# Power.net
KiCad netlist of a schematic drawn in Altium Designer
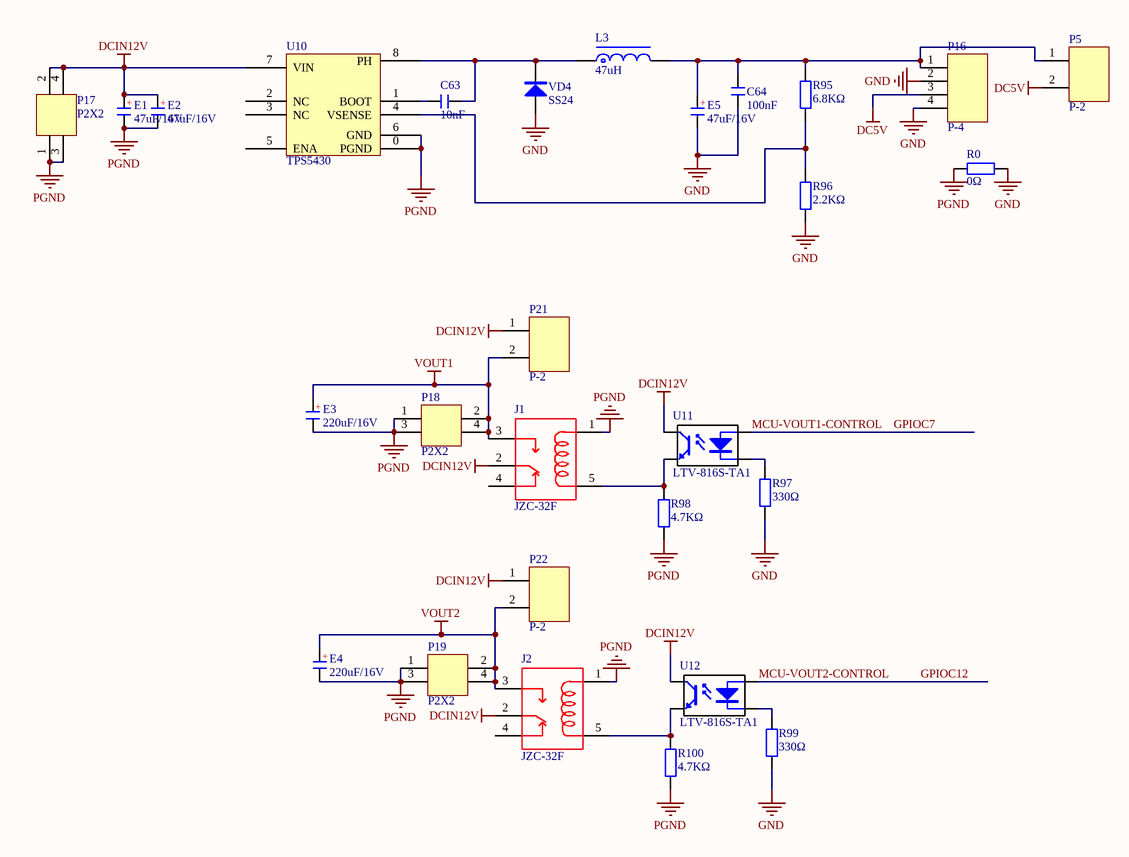
[diagram p0: Power.SchDoc]

(export (version "E")
  (design (tool "Eeschema 10.0.6"))
  (components
    (comp (ref "C63")
      (value "10nF")
      (footprint "C 0603")
      (description "无极性贴片电容")
      (fields (field (name "版权归属") "源创客"))
      (libsource (lib "ZZF_Library") (part "C 10nF"))
    )
    (comp (ref "C64")
      (value "100nF")
      (footprint "C 0603")
      (description "无极性贴片电容")
      (fields (field (name "版权归属") "源创客"))
      (libsource (lib "ZZF_Library") (part "C 100nF"))
    )
    (comp (ref "E1")
      (value "47uF/16V")
      (footprint "CD C(6032)")
      (description "贴片钽电容")
      (fields (field (name "版权归属") "源创客"))
      (libsource (lib "ZZF_Library") (part "C-CD 47uF/16V"))
    )
    (comp (ref "E2")
      (value "47uF/16V")
      (footprint "CD C(6032)")
      (description "贴片钽电容")
      (fields (field (name "版权归属") "源创客"))
      (libsource (lib "ZZF_Library") (part "C-CD 47uF/16V"))
    )
    (comp (ref "E3")
      (value "220uF/16V")
      (footprint "CD E(7343H)")
      (description "贴片钽电容")
      (fields (field (name "版权归属") "源创客"))
      (libsource (lib "ZZF_Library") (part "C-CD 220uF/16V"))
    )
    (comp (ref "E4")
      (value "220uF/16V")
      (footprint "CD E(7343H)")
      (description "贴片钽电容")
      (fields (field (name "版权归属") "源创客"))
      (libsource (lib "ZZF_Library") (part "C-CD 220uF/16V"))
    )
    (comp (ref "E5")
      (value "47uF/16V")
      (footprint "CD C(6032)")
      (description "贴片钽电容")
      (fields (field (name "版权归属") "源创客"))
      (libsource (lib "ZZF_Library") (part "C-CD 47uF/16V"))
    )
    (comp (ref "J1")
      (value "JZC-32F")
      (footprint "RELAY-ThroughHole")
      (description "继电器12V10A")
      (libsource (lib "ZZF_Library") (part "RELAY JZC-32F"))
    )
    (comp (ref "J2")
      (value "JZC-32F")
      (footprint "RELAY-ThroughHole")
      (description "继电器12V10A")
      (libsource (lib "ZZF_Library") (part "RELAY JZC-32F"))
    )
    (comp (ref "L3")
      (value "47uH")
      (footprint "L CD75")
      (description "贴片功率电感")
      (fields (field (name "版权归属") "源创客"))
      (libsource (lib "ZZF_Library") (part "L-CD  47uH"))
    )
    (comp (ref "P5")
      (value "P-2")
      (footprint "P HDR2.54-1X2")
      (description "2脚接插件")
      (libsource (lib "ZZF_Library") (part "P-2"))
    )
    (comp (ref "P16")
      (value "P-4")
      (footprint "P XH2.54-4")
      (description "4脚接插件")
      (libsource (lib "ZZF_Library") (part "P-4"))
    )
    (comp (ref "P17")
      (value "P2X2")
      (footprint "P 5557ATX4.2-2X2H")
      (description "2X2脚接插件")
      (libsource (lib "") (part "P-2X2_1"))
    )
    (comp (ref "P18")
      (value "P2X2")
      (footprint "P 5557ATX4.2-2X2H")
      (description "2X2脚接插件")
      (libsource (lib "ZZF_Library") (part "P-2X2"))
    )
    (comp (ref "P19")
      (value "P2X2")
      (footprint "P 5557ATX4.2-2X2H")
      (description "2X2脚接插件")
      (libsource (lib "ZZF_Library") (part "P-2X2"))
    )
    (comp (ref "P21")
      (value "P-2")
      (footprint "P HDR2.54-1X2")
      (description "2脚接插件")
      (libsource (lib "ZZF_Library") (part "P-2"))
    )
    (comp (ref "P22")
      (value "P-2")
      (footprint "P HDR2.54-1X2")
      (description "2脚接插件")
      (libsource (lib "ZZF_Library") (part "P-2"))
    )
    (comp (ref "R0")
      (value "0Ω")
      (footprint "R 0805")
      (description "贴片电阻")
      (fields (field (name "版权归属") "源创客"))
      (libsource (lib "ZZF_Library") (part "R 0Ω"))
    )
    (comp (ref "R95")
      (value "6.8KΩ")
      (footprint "R 0603")
      (description "贴片电阻")
      (fields (field (name "版权归属") "源创客"))
      (libsource (lib "ZZF_Library") (part "R 6.8KΩ"))
    )
    (comp (ref "R96")
      (value "2.2KΩ")
      (footprint "R 0603")
      (description "贴片电阻")
      (fields (field (name "版权归属") "源创客"))
      (libsource (lib "ZZF_Library") (part "R 2.2KΩ"))
    )
    (comp (ref "R97")
      (value "330Ω")
      (footprint "R 0805")
      (description "贴片电阻")
      (fields (field (name "版权归属") "源创客"))
      (libsource (lib "ZZF_Library") (part "R 330Ω"))
    )
    (comp (ref "R98")
      (value "4.7KΩ")
      (footprint "R 0603")
      (description "贴片电阻")
      (fields (field (name "版权归属") "源创客"))
      (libsource (lib "ZZF_Library") (part "R 4.7KΩ"))
    )
    (comp (ref "R99")
      (value "330Ω")
      (footprint "R 0805")
      (description "贴片电阻")
      (fields (field (name "版权归属") "源创客"))
      (libsource (lib "ZZF_Library") (part "R 330Ω"))
    )
    (comp (ref "R100")
      (value "4.7KΩ")
      (footprint "R 0603")
      (description "贴片电阻")
      (fields (field (name "版权归属") "源创客"))
      (libsource (lib "ZZF_Library") (part "R 4.7KΩ"))
    )
    (comp (ref "U10")
      (value "TPS5430")
      (footprint "SOP8-EP")
      (description "DCDC芯片3A")
      (libsource (lib "ZZF_Library") (part "TPS5430"))
    )
    (comp (ref "U11")
      (value "LTV-816S-TA1")
      (footprint "Optocoupler-SMD4")
      (description "光耦芯片")
      (libsource (lib "ZZF_Library") (part "Optocoupler LTV-816S-TA1"))
    )
    (comp (ref "U12")
      (value "LTV-816S-TA1")
      (footprint "Optocoupler-SMD4")
      (description "光耦芯片")
      (libsource (lib "ZZF_Library") (part "Optocoupler LTV-816S-TA1"))
    )
    (comp (ref "VD4")
      (value "SS24")
      (footprint "D SMB")
      (description "肖特基二极管")
      (fields (field (name "版权归属") "源创客"))
      (libsource (lib "ZZF_Library") (part "SS24"))
    )
  )
  (nets
    (net (code "1") (name "/GPIOC7") (class "Default")
      (node (ref "U11") (pin "1") (pinfunction "1_1") (pintype "passive"))
    )
    (net (code "2") (name "/GPIOC12") (class "Default")
      (node (ref "U12") (pin "1") (pinfunction "1_1") (pintype "passive"))
    )
    (net (code "3") (name "DC5V") (class "Default")
      (node (ref "P16") (pin "3") (pinfunction "3_3") (pintype "passive"))
      (node (ref "P5") (pin "2") (pinfunction "2_2") (pintype "passive"))
    )
    (net (code "4") (name "DCIN12V") (class "Default")
      (node (ref "E1") (pin "A") (pinfunction "+_A") (pintype "passive"))
      (node (ref "E2") (pin "A") (pinfunction "+_A") (pintype "passive"))
      (node (ref "J1") (pin "2") (pinfunction "IN-_2") (pintype "passive"))
      (node (ref "J2") (pin "2") (pinfunction "IN-_2") (pintype "passive"))
      (node (ref "P17") (pin "2") (pinfunction "2_2") (pintype "passive"))
      (node (ref "P17") (pin "4") (pinfunction "4_4") (pintype "passive"))
      (node (ref "P21") (pin "1") (pinfunction "1_1") (pintype "passive"))
      (node (ref "P22") (pin "1") (pinfunction "1_1") (pintype "passive"))
      (node (ref "U10") (pin "7") (pinfunction "VIN_7") (pintype "passive"))
      (node (ref "U11") (pin "4") (pinfunction "4_4") (pintype "passive"))
      (node (ref "U12") (pin "4") (pinfunction "4_4") (pintype "passive"))
    )
    (net (code "5") (name "GND") (class "Default")
      (node (ref "C64") (pin "1") (pinfunction "1_1") (pintype "passive"))
      (node (ref "E5") (pin "K") (pinfunction "-_K") (pintype "passive"))
      (node (ref "P16") (pin "2") (pinfunction "2_2") (pintype "passive"))
      (node (ref "P16") (pin "4") (pinfunction "4_4") (pintype "passive"))
      (node (ref "R0") (pin "2") (pinfunction "2_2") (pintype "passive"))
      (node (ref "R96") (pin "1") (pinfunction "1_1") (pintype "passive"))
      (node (ref "R97") (pin "1") (pinfunction "1_1") (pintype "passive"))
      (node (ref "R99") (pin "1") (pinfunction "1_1") (pintype "passive"))
      (node (ref "VD4") (pin "A") (pinfunction "A_A") (pintype "passive"))
    )
    (net (code "6") (name "Net-(E5-+)") (class "Default")
      (node (ref "C64") (pin "2") (pinfunction "2_2") (pintype "passive"))
      (node (ref "E5") (pin "A") (pinfunction "+_A") (pintype "passive"))
      (node (ref "L3") (pin "2") (pinfunction "2_2") (pintype "passive"))
      (node (ref "P16") (pin "1") (pinfunction "1_1") (pintype "passive"))
      (node (ref "P5") (pin "1") (pinfunction "1_1") (pintype "passive"))
      (node (ref "R95") (pin "2") (pinfunction "2_2") (pintype "passive"))
    )
    (net (code "7") (name "Net-(J1-OUT-)") (class "Default")
      (node (ref "J1") (pin "5") (pinfunction "OUT-_5") (pintype "passive"))
      (node (ref "R98") (pin "2") (pinfunction "2_2") (pintype "passive"))
      (node (ref "U11") (pin "3") (pinfunction "3_3") (pintype "passive"))
    )
    (net (code "8") (name "Net-(J2-OUT-)") (class "Default")
      (node (ref "J2") (pin "5") (pinfunction "OUT-_5") (pintype "passive"))
      (node (ref "R100") (pin "2") (pinfunction "2_2") (pintype "passive"))
      (node (ref "U12") (pin "3") (pinfunction "3_3") (pintype "passive"))
    )
    (net (code "9") (name "Net-(R97-Pad2)") (class "Default")
      (node (ref "R97") (pin "2") (pinfunction "2_2") (pintype "passive"))
      (node (ref "U11") (pin "2") (pinfunction "2_2") (pintype "passive"))
    )
    (net (code "10") (name "Net-(R99-Pad2)") (class "Default")
      (node (ref "R99") (pin "2") (pinfunction "2_2") (pintype "passive"))
      (node (ref "U12") (pin "2") (pinfunction "2_2") (pintype "passive"))
    )
    (net (code "11") (name "Net-(U10-BOOT)") (class "Default")
      (node (ref "C63") (pin "1") (pinfunction "1_1") (pintype "passive"))
      (node (ref "U10") (pin "1") (pinfunction "BOOT_1") (pintype "passive"))
    )
    (net (code "12") (name "Net-(U10-PH)") (class "Default")
      (node (ref "C63") (pin "2") (pinfunction "2_2") (pintype "passive"))
      (node (ref "L3") (pin "1") (pinfunction "1_1") (pintype "passive"))
      (node (ref "U10") (pin "8") (pinfunction "PH_8") (pintype "passive"))
      (node (ref "VD4") (pin "K") (pinfunction "K_K") (pintype "passive"))
    )
    (net (code "13") (name "Net-(U10-VSENSE)") (class "Default")
      (node (ref "R95") (pin "1") (pinfunction "1_1") (pintype "passive"))
      (node (ref "R96") (pin "2") (pinfunction "2_2") (pintype "passive"))
      (node (ref "U10") (pin "4") (pinfunction "VSENSE_4") (pintype "passive"))
    )
    (net (code "14") (name "PGND") (class "Default")
      (node (ref "E1") (pin "K") (pinfunction "-_K") (pintype "passive"))
      (node (ref "E2") (pin "K") (pinfunction "-_K") (pintype "passive"))
      (node (ref "E3") (pin "K") (pinfunction "-_K") (pintype "passive"))
      (node (ref "E4") (pin "K") (pinfunction "-_K") (pintype "passive"))
      (node (ref "J1") (pin "1") (pinfunction "OUT+_1") (pintype "passive"))
      (node (ref "J2") (pin "1") (pinfunction "OUT+_1") (pintype "passive"))
      (node (ref "P17") (pin "1") (pinfunction "1_1") (pintype "passive"))
      (node (ref "P17") (pin "3") (pinfunction "3_3") (pintype "passive"))
      (node (ref "P18") (pin "1") (pinfunction "1_1") (pintype "passive"))
      (node (ref "P18") (pin "3") (pinfunction "3_3") (pintype "passive"))
      (node (ref "P19") (pin "1") (pinfunction "1_1") (pintype "passive"))
      (node (ref "P19") (pin "3") (pinfunction "3_3") (pintype "passive"))
      (node (ref "R0") (pin "1") (pinfunction "1_1") (pintype "passive"))
      (node (ref "R100") (pin "1") (pinfunction "1_1") (pintype "passive"))
      (node (ref "R98") (pin "1") (pinfunction "1_1") (pintype "passive"))
      (node (ref "U10") (pin "0") (pinfunction "PGND_0") (pintype "passive"))
      (node (ref "U10") (pin "6") (pinfunction "GND_6") (pintype "passive"))
    )
    (net (code "15") (name "VOUT1") (class "Default")
      (node (ref "E3") (pin "A") (pinfunction "+_A") (pintype "passive"))
      (node (ref "J1") (pin "3") (pinfunction "IN+_3") (pintype "passive"))
      (node (ref "P18") (pin "2") (pinfunction "2_2") (pintype "passive"))
      (node (ref "P18") (pin "4") (pinfunction "4_4") (pintype "passive"))
      (node (ref "P21") (pin "2") (pinfunction "2_2") (pintype "passive"))
    )
    (net (code "16") (name "VOUT2") (class "Default")
      (node (ref "E4") (pin "A") (pinfunction "+_A") (pintype "passive"))
      (node (ref "J2") (pin "3") (pinfunction "IN+_3") (pintype "passive"))
      (node (ref "P19") (pin "2") (pinfunction "2_2") (pintype "passive"))
      (node (ref "P19") (pin "4") (pinfunction "4_4") (pintype "passive"))
      (node (ref "P22") (pin "2") (pinfunction "2_2") (pintype "passive"))
    )
    (net (code "17") (name "unconnected-(J1-IN--Pad4)") (class "Default")
      (node (ref "J1") (pin "4") (pinfunction "IN-_4") (pintype "passive"))
    )
    (net (code "18") (name "unconnected-(J2-IN--Pad4)") (class "Default")
      (node (ref "J2") (pin "4") (pinfunction "IN-_4") (pintype "passive"))
    )
    (net (code "19") (name "unconnected-(U10-ENA-Pad5)") (class "Default")
      (node (ref "U10") (pin "5") (pinfunction "ENA_5") (pintype "passive"))
    )
    (net (code "20") (name "unconnected-(U10-NC-Pad2)") (class "Default")
      (node (ref "U10") (pin "2") (pinfunction "NC_2") (pintype "passive"))
    )
    (net (code "21") (name "unconnected-(U10-NC-Pad3)") (class "Default")
      (node (ref "U10") (pin "3") (pinfunction "NC_3") (pintype "passive"))
    )
  )
)
